# Sheet2.net
KiCad netlist of a schematic drawn in Altium Designer
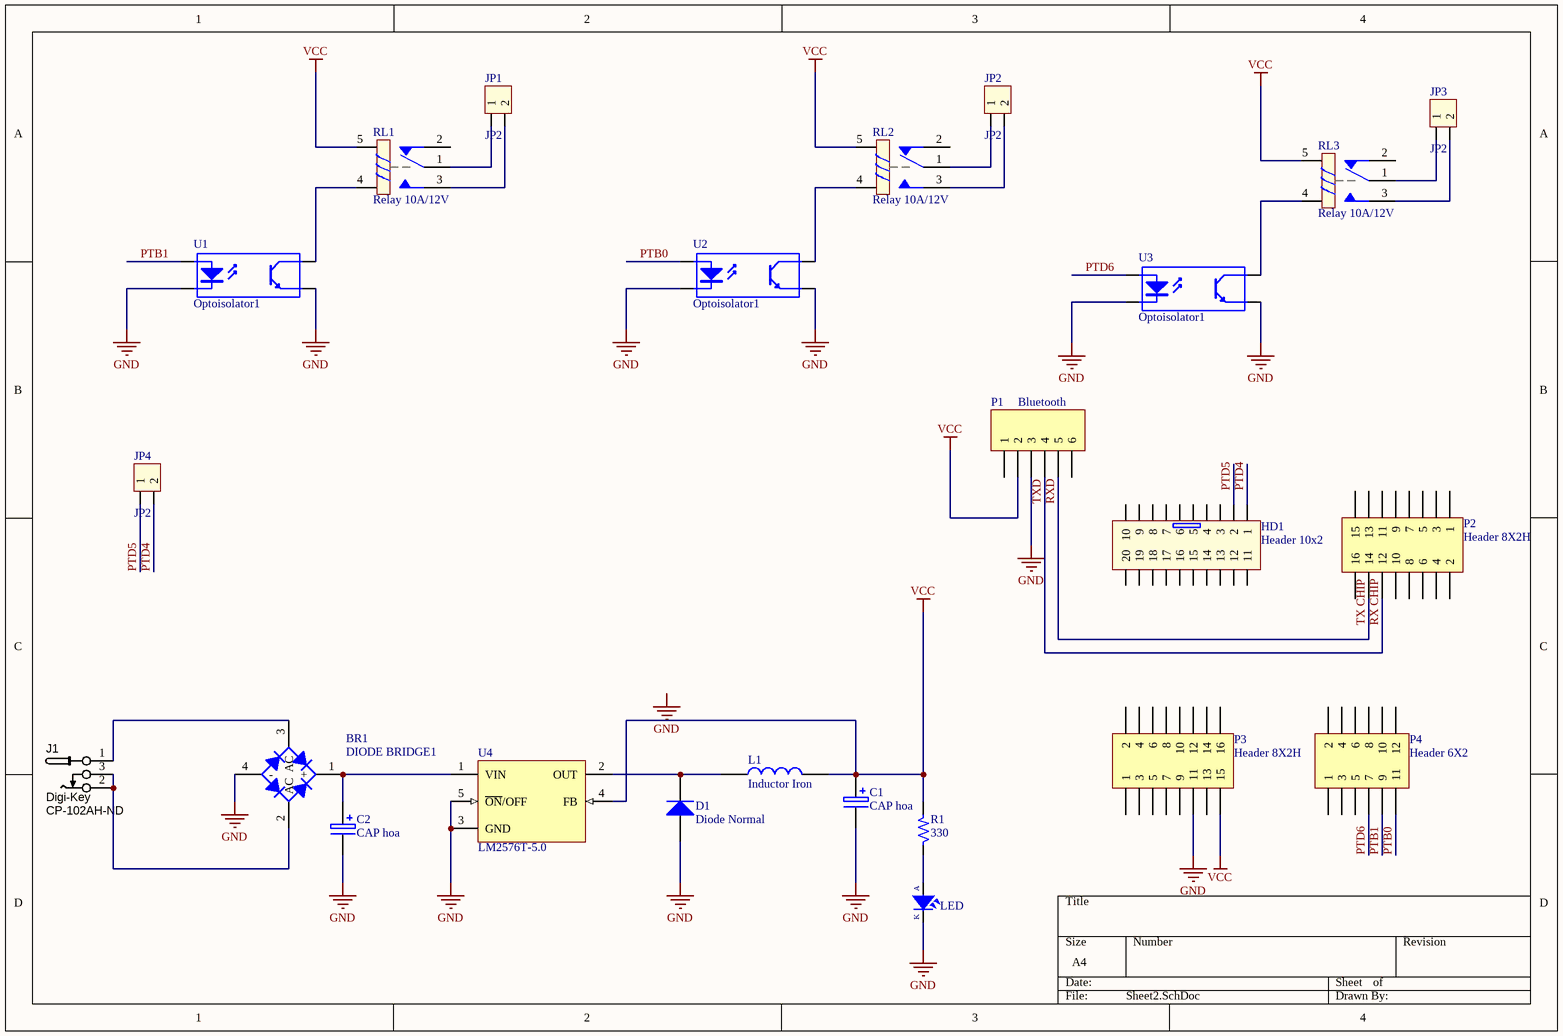
[diagram p0: Sheet2.SchDoc]

(export (version "E")
  (design (tool "Eeschema 10.0.6"))
  (components
    (comp (ref "BR1")
      (value "DIODE BRIDGE1")
      (footprint "CAU 1A")
      (libsource (lib "My library altium") (part "DIODE BRIDGE1"))
    )
    (comp (ref "C1")
      (value "CAP hoa")
      (footprint "CP1.5/3.4")
      (description "Cap")
      (libsource (lib "My library altium") (part "CAP hoa"))
    )
    (comp (ref "C2")
      (value "CAP hoa")
      (footprint "CP1.5/3.4")
      (description "Cap")
      (libsource (lib "My library altium") (part "CAP hoa"))
    )
    (comp (ref "D1")
      (value "Diode Normal")
      (footprint "DIODE/NOM/0.5A")
      (fields (field (name "PUBLISHER") "Altium Limited"))
      (libsource (lib "My library altium") (part "Diode Normal"))
    )
    (comp (ref "HD1")
      (value "Header 10x2")
      (footprint "Hed2X10")
      (libsource (lib "syhaunguyen") (part "HED10X2"))
    )
    (comp (ref "J1")
      (value "CONN_PWR_JACK_2.1x5.5mm")
      (footprint "CONN_PWR_JACK_2.1x5.5mm")
      (description "Power Connector, THT, 2.1mm ID, 5.5mm OD")
      (fields (field (name "SUPPLIER 1") "Digi-Key") (field (name "SUPPLIER PART NUMBER 1") "CP-102AH-ND"))
      (libsource (lib "My library altium") (part "CONN_PWR_JACK_2.1x5.5mm"))
    )
    (comp (ref "JP1")
      (value "JP2")
      (footprint "CON2")
      (description "Connector 2")
      (libsource (lib "syhaunguyen") (part "Con2"))
    )
    (comp (ref "JP2")
      (value "JP2")
      (footprint "CON2")
      (description "Connector 2")
      (libsource (lib "syhaunguyen") (part "Con2"))
    )
    (comp (ref "JP3")
      (value "JP2")
      (footprint "CON2")
      (description "Connector 2")
      (libsource (lib "syhaunguyen") (part "Con2"))
    )
    (comp (ref "JP4")
      (value "JP2")
      (footprint "CON2")
      (description "Connector 2")
      (libsource (lib "syhaunguyen") (part "Con2"))
    )
    (comp (ref "L1")
      (value "Inductor Iron")
      (footprint "PE-92102-100uH")
      (description "Inductor")
      (libsource (lib "My library altium") (part "Inductor Iron"))
    )
    (comp (ref "LED1")
      (value "LED")
      (footprint "LED-3")
      (description "LED Single colour Green and Red")
      (libsource (lib "My library altium") (part "LED"))
    )
    (comp (ref "P1")
      (value "Bluetooth")
      (footprint "HDR1X6")
      (description "Header, 6-Pin")
      (fields (field (name "PUBLISHER") "Altium Limited"))
      (libsource (lib "Miscellaneous Connectors") (part "Header 6"))
    )
    (comp (ref "P2")
      (value "Header 8X2H")
      (footprint "HDR2X8H")
      (description "Header, 8-Pin, Dual row, Right Angle")
      (fields (field (name "PUBLISHER") "Altium Limited"))
      (libsource (lib "") (part "Header 8X2H_1"))
    )
    (comp (ref "P3")
      (value "Header 8X2H")
      (footprint "HDR2X8H")
      (description "Header, 8-Pin, Dual row, Right Angle")
      (fields (field (name "PUBLISHER") "Altium Limited"))
      (libsource (lib "My library altium") (part "Header 8X2H"))
    )
    (comp (ref "P4")
      (value "Header 6X2")
      (footprint "HDR2X6")
      (description "Header, 6-Pin, Dual row")
      (fields (field (name "PUBLISHER") "Altium Limited"))
      (libsource (lib "My library altium") (part "Header 6X2"))
    )
    (comp (ref "R1")
      (value "330")
      (footprint "R1/4W")
      (description "Res")
      (libsource (lib "My library altium") (part "Res"))
    )
    (comp (ref "RL1")
      (value "Relay 10A/12V")
      (footprint "RL_SPDT_10A")
      (description "Relay SPDT,10A - 12VDC 5 Pin")
      (libsource (lib "syhaunguyen") (part "Relay 1"))
    )
    (comp (ref "RL2")
      (value "Relay 10A/12V")
      (footprint "RL_SPDT_10A")
      (description "Relay SPDT,10A - 12VDC 5 Pin")
      (libsource (lib "syhaunguyen") (part "Relay 1"))
    )
    (comp (ref "RL3")
      (value "Relay 10A/12V")
      (footprint "RL_SPDT_10A")
      (description "Relay SPDT,10A - 12VDC 5 Pin")
      (libsource (lib "syhaunguyen") (part "Relay 1"))
    )
    (comp (ref "U1")
      (value "Optoisolator1")
      (footprint "DIP-4")
      (description "4-Pin Phototransistor Optocoupler")
      (fields (field (name "PUBLISHER") "Altium Limited"))
      (libsource (lib "Miscellaneous Devices") (part "Optoisolator1"))
    )
    (comp (ref "U2")
      (value "Optoisolator1")
      (footprint "DIP-4")
      (description "4-Pin Phototransistor Optocoupler")
      (fields (field (name "PUBLISHER") "Altium Limited"))
      (libsource (lib "Miscellaneous Devices") (part "Optoisolator1"))
    )
    (comp (ref "U3")
      (value "Optoisolator1")
      (footprint "DIP-4")
      (description "4-Pin Phototransistor Optocoupler")
      (fields (field (name "PUBLISHER") "Altium Limited"))
      (libsource (lib "Miscellaneous Devices") (part "Optoisolator1"))
    )
    (comp (ref "U4")
      (value "LM2576T-5.0")
      (footprint "LM2576t")
      (description "SIMPLE SWITCHER; 3A Step-Down Voltage Regulator")
      (fields
        (field (name "MANUFACTURER") "National Semiconductor")
        (field (name "DIGIKEYPARTNUMBER") "LM2576T-5.0-ND")
        (field (name "PUBLISHER") "Altium Limited")
      )
      (libsource (lib "My library altium") (part "LM2576T-5.0"))
    )
  )
  (nets
    (net (code "1") (name "/PTB0") (class "Default")
      (node (ref "P4") (pin "11") (pinfunction "11_11") (pintype "passive"))
      (node (ref "U2") (pin "1") (pinfunction "A_1") (pintype "passive"))
    )
    (net (code "2") (name "/PTB1") (class "Default")
      (node (ref "P4") (pin "9") (pinfunction "9_9") (pintype "passive"))
      (node (ref "U1") (pin "1") (pinfunction "A_1") (pintype "passive"))
    )
    (net (code "3") (name "/PTD4") (class "Default")
      (node (ref "HD1") (pin "1") (pinfunction "1_1") (pintype "passive"))
      (node (ref "JP4") (pin "2") (pinfunction "2_2") (pintype "passive"))
    )
    (net (code "4") (name "/PTD5") (class "Default")
      (node (ref "HD1") (pin "2") (pinfunction "2_2") (pintype "passive"))
      (node (ref "JP4") (pin "1") (pinfunction "1_1") (pintype "passive"))
    )
    (net (code "5") (name "/PTD6") (class "Default")
      (node (ref "P4") (pin "7") (pinfunction "7_7") (pintype "passive"))
      (node (ref "U3") (pin "1") (pinfunction "A_1") (pintype "passive"))
    )
    (net (code "6") (name "/RX CHIP") (class "Default")
      (node (ref "P1") (pin "4") (pinfunction "4_4") (pintype "passive"))
      (node (ref "P2") (pin "12") (pinfunction "12_12") (pintype "passive"))
    )
    (net (code "7") (name "/RXD") (class "Default")
      (node (ref "P1") (pin "5") (pinfunction "5_5") (pintype "passive"))
      (node (ref "P2") (pin "14") (pinfunction "14_14") (pintype "passive"))
    )
    (net (code "8") (name "GND") (class "Default")
      (node (ref "BR1") (pin "4") (pinfunction "-_4") (pintype "passive"))
      (node (ref "C1") (pin "2") (pintype "passive"))
      (node (ref "C2") (pin "2") (pintype "passive"))
      (node (ref "D1") (pin "1") (pinfunction "A_1") (pintype "passive"))
      (node (ref "LED1") (pin "2") (pinfunction "K_2") (pintype "passive"))
      (node (ref "P1") (pin "3") (pinfunction "3_3") (pintype "passive"))
      (node (ref "P3") (pin "11") (pinfunction "11_11") (pintype "passive"))
      (node (ref "U1") (pin "2") (pinfunction "K_2") (pintype "passive"))
      (node (ref "U1") (pin "3") (pinfunction "E_3") (pintype "passive"))
      (node (ref "U2") (pin "2") (pinfunction "K_2") (pintype "passive"))
      (node (ref "U2") (pin "3") (pinfunction "E_3") (pintype "passive"))
      (node (ref "U3") (pin "2") (pinfunction "K_2") (pintype "passive"))
      (node (ref "U3") (pin "3") (pinfunction "E_3") (pintype "passive"))
      (node (ref "U4") (pin "3") (pinfunction "GND_3") (pintype "power_in"))
      (node (ref "U4") (pin "5") (pinfunction "~{ON}/OFF_5") (pintype "input"))
    )
    (net (code "9") (name "Net-(BR1-+)") (class "Default")
      (node (ref "BR1") (pin "1") (pinfunction "+_1") (pintype "passive"))
      (node (ref "C2") (pin "1") (pintype "passive"))
      (node (ref "U4") (pin "1") (pinfunction "VIN_1") (pintype "power_in"))
    )
    (net (code "10") (name "Net-(BR1-AC-Pad2)") (class "Default")
      (node (ref "BR1") (pin "2") (pinfunction "AC_2") (pintype "passive"))
      (node (ref "J1") (pin "2") (pinfunction "2_2") (pintype "passive"))
      (node (ref "J1") (pin "3") (pinfunction "3_3") (pintype "passive"))
    )
    (net (code "11") (name "Net-(BR1-AC-Pad3)") (class "Default")
      (node (ref "BR1") (pin "3") (pinfunction "AC_3") (pintype "passive"))
      (node (ref "J1") (pin "1") (pinfunction "1_1") (pintype "passive"))
    )
    (net (code "12") (name "Net-(D1-K)") (class "Default")
      (node (ref "D1") (pin "2") (pinfunction "K_2") (pintype "passive"))
      (node (ref "L1") (pin "1") (pinfunction "1_1") (pintype "passive"))
      (node (ref "U4") (pin "2") (pinfunction "OUT_2") (pintype "power_in"))
    )
    (net (code "13") (name "Net-(JP1-Pad1)") (class "Default")
      (node (ref "JP1") (pin "1") (pinfunction "1_1") (pintype "passive"))
      (node (ref "RL1") (pin "1") (pinfunction "1_1") (pintype "passive"))
    )
    (net (code "14") (name "Net-(JP1-Pad2)") (class "Default")
      (node (ref "JP1") (pin "2") (pinfunction "2_2") (pintype "passive"))
      (node (ref "RL1") (pin "3") (pinfunction "3_3") (pintype "passive"))
    )
    (net (code "15") (name "Net-(JP2-Pad1)") (class "Default")
      (node (ref "JP2") (pin "1") (pinfunction "1_1") (pintype "passive"))
      (node (ref "RL2") (pin "1") (pinfunction "1_1") (pintype "passive"))
    )
    (net (code "16") (name "Net-(JP2-Pad2)") (class "Default")
      (node (ref "JP2") (pin "2") (pinfunction "2_2") (pintype "passive"))
      (node (ref "RL2") (pin "3") (pinfunction "3_3") (pintype "passive"))
    )
    (net (code "17") (name "Net-(JP3-Pad1)") (class "Default")
      (node (ref "JP3") (pin "1") (pinfunction "1_1") (pintype "passive"))
      (node (ref "RL3") (pin "1") (pinfunction "1_1") (pintype "passive"))
    )
    (net (code "18") (name "Net-(JP3-Pad2)") (class "Default")
      (node (ref "JP3") (pin "2") (pinfunction "2_2") (pintype "passive"))
      (node (ref "RL3") (pin "3") (pinfunction "3_3") (pintype "passive"))
    )
    (net (code "19") (name "Net-(LED1-A)") (class "Default")
      (node (ref "LED1") (pin "1") (pinfunction "A_1") (pintype "passive"))
      (node (ref "R1") (pin "1") (pinfunction "1_1") (pintype "passive"))
    )
    (net (code "20") (name "Net-(U1-C)") (class "Default")
      (node (ref "RL1") (pin "4") (pinfunction "4_4") (pintype "passive"))
      (node (ref "U1") (pin "4") (pinfunction "C_4") (pintype "passive"))
    )
    (net (code "21") (name "Net-(U2-C)") (class "Default")
      (node (ref "RL2") (pin "4") (pinfunction "4_4") (pintype "passive"))
      (node (ref "U2") (pin "4") (pinfunction "C_4") (pintype "passive"))
    )
    (net (code "22") (name "Net-(U3-C)") (class "Default")
      (node (ref "RL3") (pin "4") (pinfunction "4_4") (pintype "passive"))
      (node (ref "U3") (pin "4") (pinfunction "C_4") (pintype "passive"))
    )
    (net (code "23") (name "VCC") (class "Default")
      (node (ref "C1") (pin "1") (pintype "passive"))
      (node (ref "L1") (pin "2") (pinfunction "2_2") (pintype "passive"))
      (node (ref "P1") (pin "2") (pinfunction "2_2") (pintype "passive"))
      (node (ref "P3") (pin "15") (pinfunction "15_15") (pintype "passive"))
      (node (ref "R1") (pin "2") (pinfunction "2_2") (pintype "passive"))
      (node (ref "RL1") (pin "5") (pinfunction "5_5") (pintype "passive"))
      (node (ref "RL2") (pin "5") (pinfunction "5_5") (pintype "passive"))
      (node (ref "RL3") (pin "5") (pinfunction "5_5") (pintype "passive"))
      (node (ref "U4") (pin "4") (pinfunction "FB_4") (pintype "input"))
    )
    (net (code "24") (name "unconnected-(HD1-Pad3)") (class "Default")
      (node (ref "HD1") (pin "3") (pinfunction "3_3") (pintype "passive"))
    )
    (net (code "25") (name "unconnected-(HD1-Pad4)") (class "Default")
      (node (ref "HD1") (pin "4") (pinfunction "4_4") (pintype "passive"))
    )
    (net (code "26") (name "unconnected-(HD1-Pad5)") (class "Default")
      (node (ref "HD1") (pin "5") (pinfunction "5_5") (pintype "passive"))
    )
    (net (code "27") (name "unconnected-(HD1-Pad6)") (class "Default")
      (node (ref "HD1") (pin "6") (pinfunction "6_6") (pintype "passive"))
    )
    (net (code "28") (name "unconnected-(HD1-Pad7)") (class "Default")
      (node (ref "HD1") (pin "7") (pinfunction "7_7") (pintype "passive"))
    )
    (net (code "29") (name "unconnected-(HD1-Pad8)") (class "Default")
      (node (ref "HD1") (pin "8") (pinfunction "8_8") (pintype "passive"))
    )
    (net (code "30") (name "unconnected-(HD1-Pad9)") (class "Default")
      (node (ref "HD1") (pin "9") (pinfunction "9_9") (pintype "passive"))
    )
    (net (code "31") (name "unconnected-(HD1-Pad10)") (class "Default")
      (node (ref "HD1") (pin "10") (pinfunction "10_10") (pintype "passive"))
    )
    (net (code "32") (name "unconnected-(HD1-Pad11)") (class "Default")
      (node (ref "HD1") (pin "11") (pinfunction "11_11") (pintype "passive"))
    )
    (net (code "33") (name "unconnected-(HD1-Pad12)") (class "Default")
      (node (ref "HD1") (pin "12") (pinfunction "12_12") (pintype "passive"))
    )
    (net (code "34") (name "unconnected-(HD1-Pad13)") (class "Default")
      (node (ref "HD1") (pin "13") (pinfunction "13_13") (pintype "passive"))
    )
    (net (code "35") (name "unconnected-(HD1-Pad14)") (class "Default")
      (node (ref "HD1") (pin "14") (pinfunction "14_14") (pintype "passive"))
    )
    (net (code "36") (name "unconnected-(HD1-Pad15)") (class "Default")
      (node (ref "HD1") (pin "15") (pinfunction "15_15") (pintype "passive"))
    )
    (net (code "37") (name "unconnected-(HD1-Pad16)") (class "Default")
      (node (ref "HD1") (pin "16") (pinfunction "16_16") (pintype "passive"))
    )
    (net (code "38") (name "unconnected-(HD1-Pad17)") (class "Default")
      (node (ref "HD1") (pin "17") (pinfunction "17_17") (pintype "passive"))
    )
    (net (code "39") (name "unconnected-(HD1-Pad18)") (class "Default")
      (node (ref "HD1") (pin "18") (pinfunction "18_18") (pintype "passive"))
    )
    (net (code "40") (name "unconnected-(HD1-Pad19)") (class "Default")
      (node (ref "HD1") (pin "19") (pinfunction "19_19") (pintype "passive"))
    )
    (net (code "41") (name "unconnected-(HD1-Pad20)") (class "Default")
      (node (ref "HD1") (pin "20") (pinfunction "20_20") (pintype "passive"))
    )
    (net (code "42") (name "unconnected-(P1-Pad1)") (class "Default")
      (node (ref "P1") (pin "1") (pinfunction "1_1") (pintype "passive"))
    )
    (net (code "43") (name "unconnected-(P1-Pad6)") (class "Default")
      (node (ref "P1") (pin "6") (pinfunction "6_6") (pintype "passive"))
    )
    (net (code "44") (name "unconnected-(P2-Pad1)") (class "Default")
      (node (ref "P2") (pin "1") (pinfunction "1_1") (pintype "passive"))
    )
    (net (code "45") (name "unconnected-(P2-Pad2)") (class "Default")
      (node (ref "P2") (pin "2") (pinfunction "2_2") (pintype "passive"))
    )
    (net (code "46") (name "unconnected-(P2-Pad3)") (class "Default")
      (node (ref "P2") (pin "3") (pinfunction "3_3") (pintype "passive"))
    )
    (net (code "47") (name "unconnected-(P2-Pad4)") (class "Default")
      (node (ref "P2") (pin "4") (pinfunction "4_4") (pintype "passive"))
    )
    (net (code "48") (name "unconnected-(P2-Pad5)") (class "Default")
      (node (ref "P2") (pin "5") (pinfunction "5_5") (pintype "passive"))
    )
    (net (code "49") (name "unconnected-(P2-Pad6)") (class "Default")
      (node (ref "P2") (pin "6") (pinfunction "6_6") (pintype "passive"))
    )
    (net (code "50") (name "unconnected-(P2-Pad7)") (class "Default")
      (node (ref "P2") (pin "7") (pinfunction "7_7") (pintype "passive"))
    )
    (net (code "51") (name "unconnected-(P2-Pad8)") (class "Default")
      (node (ref "P2") (pin "8") (pinfunction "8_8") (pintype "passive"))
    )
    (net (code "52") (name "unconnected-(P2-Pad9)") (class "Default")
      (node (ref "P2") (pin "9") (pinfunction "9_9") (pintype "passive"))
    )
    (net (code "53") (name "unconnected-(P2-Pad10)") (class "Default")
      (node (ref "P2") (pin "10") (pinfunction "10_10") (pintype "passive"))
    )
    (net (code "54") (name "unconnected-(P2-Pad11)") (class "Default")
      (node (ref "P2") (pin "11") (pinfunction "11_11") (pintype "passive"))
    )
    (net (code "55") (name "unconnected-(P2-Pad13)") (class "Default")
      (node (ref "P2") (pin "13") (pinfunction "13_13") (pintype "passive"))
    )
    (net (code "56") (name "unconnected-(P2-Pad15)") (class "Default")
      (node (ref "P2") (pin "15") (pinfunction "15_15") (pintype "passive"))
    )
    (net (code "57") (name "unconnected-(P2-Pad16)") (class "Default")
      (node (ref "P2") (pin "16") (pinfunction "16_16") (pintype "passive"))
    )
    (net (code "58") (name "unconnected-(P3-Pad1)") (class "Default")
      (node (ref "P3") (pin "1") (pinfunction "1_1") (pintype "passive"))
    )
    (net (code "59") (name "unconnected-(P3-Pad2)") (class "Default")
      (node (ref "P3") (pin "2") (pinfunction "2_2") (pintype "passive"))
    )
    (net (code "60") (name "unconnected-(P3-Pad3)") (class "Default")
      (node (ref "P3") (pin "3") (pinfunction "3_3") (pintype "passive"))
    )
    (net (code "61") (name "unconnected-(P3-Pad4)") (class "Default")
      (node (ref "P3") (pin "4") (pinfunction "4_4") (pintype "passive"))
    )
    (net (code "62") (name "unconnected-(P3-Pad5)") (class "Default")
      (node (ref "P3") (pin "5") (pinfunction "5_5") (pintype "passive"))
    )
    (net (code "63") (name "unconnected-(P3-Pad6)") (class "Default")
      (node (ref "P3") (pin "6") (pinfunction "6_6") (pintype "passive"))
    )
    (net (code "64") (name "unconnected-(P3-Pad7)") (class "Default")
      (node (ref "P3") (pin "7") (pinfunction "7_7") (pintype "passive"))
    )
    (net (code "65") (name "unconnected-(P3-Pad8)") (class "Default")
      (node (ref "P3") (pin "8") (pinfunction "8_8") (pintype "passive"))
    )
    (net (code "66") (name "unconnected-(P3-Pad9)") (class "Default")
      (node (ref "P3") (pin "9") (pinfunction "9_9") (pintype "passive"))
    )
    (net (code "67") (name "unconnected-(P3-Pad10)") (class "Default")
      (node (ref "P3") (pin "10") (pinfunction "10_10") (pintype "passive"))
    )
    (net (code "68") (name "unconnected-(P3-Pad12)") (class "Default")
      (node (ref "P3") (pin "12") (pinfunction "12_12") (pintype "passive"))
    )
    (net (code "69") (name "unconnected-(P3-Pad13)") (class "Default")
      (node (ref "P3") (pin "13") (pinfunction "13_13") (pintype "passive"))
    )
    (net (code "70") (name "unconnected-(P3-Pad14)") (class "Default")
      (node (ref "P3") (pin "14") (pinfunction "14_14") (pintype "passive"))
    )
    (net (code "71") (name "unconnected-(P3-Pad16)") (class "Default")
      (node (ref "P3") (pin "16") (pinfunction "16_16") (pintype "passive"))
    )
    (net (code "72") (name "unconnected-(P4-Pad1)") (class "Default")
      (node (ref "P4") (pin "1") (pinfunction "1_1") (pintype "passive"))
    )
    (net (code "73") (name "unconnected-(P4-Pad2)") (class "Default")
      (node (ref "P4") (pin "2") (pinfunction "2_2") (pintype "passive"))
    )
    (net (code "74") (name "unconnected-(P4-Pad3)") (class "Default")
      (node (ref "P4") (pin "3") (pinfunction "3_3") (pintype "passive"))
    )
    (net (code "75") (name "unconnected-(P4-Pad4)") (class "Default")
      (node (ref "P4") (pin "4") (pinfunction "4_4") (pintype "passive"))
    )
    (net (code "76") (name "unconnected-(P4-Pad5)") (class "Default")
      (node (ref "P4") (pin "5") (pinfunction "5_5") (pintype "passive"))
    )
    (net (code "77") (name "unconnected-(P4-Pad6)") (class "Default")
      (node (ref "P4") (pin "6") (pinfunction "6_6") (pintype "passive"))
    )
    (net (code "78") (name "unconnected-(P4-Pad8)") (class "Default")
      (node (ref "P4") (pin "8") (pinfunction "8_8") (pintype "passive"))
    )
    (net (code "79") (name "unconnected-(P4-Pad10)") (class "Default")
      (node (ref "P4") (pin "10") (pinfunction "10_10") (pintype "passive"))
    )
    (net (code "80") (name "unconnected-(P4-Pad12)") (class "Default")
      (node (ref "P4") (pin "12") (pinfunction "12_12") (pintype "passive"))
    )
    (net (code "81") (name "unconnected-(RL1-Pad2)") (class "Default")
      (node (ref "RL1") (pin "2") (pinfunction "2_2") (pintype "passive"))
    )
    (net (code "82") (name "unconnected-(RL2-Pad2)") (class "Default")
      (node (ref "RL2") (pin "2") (pinfunction "2_2") (pintype "passive"))
    )
    (net (code "83") (name "unconnected-(RL3-Pad2)") (class "Default")
      (node (ref "RL3") (pin "2") (pinfunction "2_2") (pintype "passive"))
    )
  )
)
